# IO.net
KiCad netlist of a schematic drawn in Altium Designer
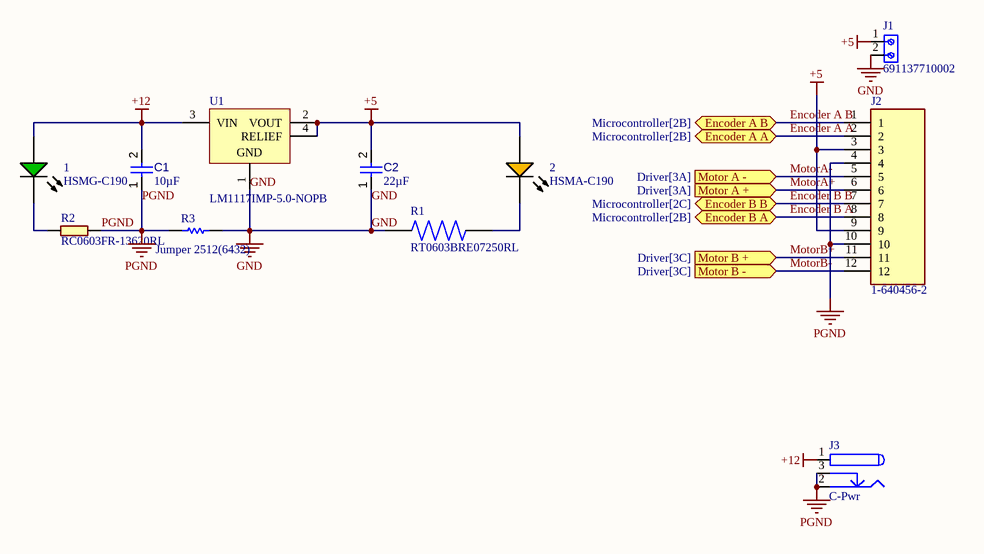
[diagram p0: IO.SchDoc]

(export (version "E")
  (design (tool "Eeschema 10.0.6"))
  (components
    (comp (ref "1")
      (value "HSMG-C190")
      (footprint "AVAG-HSMX-C190_V")
      (description "LED Uni-Color Green, 52 mW, 20 mA, -40 to 85 degC, 2-Pin SMD, RoHS, Tape and Reel")
      (fields (field (name "POWER") "52mW") (field (name "MANUFACTURER") "Avago"))
      (libsource (lib "Ryan Nedjabat") (part "LED-GREEN-AK-2"))
    )
    (comp (ref "2")
      (value "HSMA-C190")
      (footprint "AVAG-HSMX-C190_V")
      (description "LED Uni-Color Amber, 60 mW, 20 mA, -40 to 85 degC, 2-Pin SMD, RoHS, Tape and Reel")
      (fields (field (name "POWER") "60mW") (field (name "MANUFACTURER") "Avago"))
      (libsource (lib "Ryan Nedjabat") (part "LED-AMBER-AK-2"))
    )
    (comp (ref "C1")
      (value "10µF")
      (footprint "CAPC0603(1608)100_L")
      (description "Chip Capacitor, 10µF +/-20%, 10V, 0603, Thickness 1 mm")
      (fields (field (name "TOLERANCE") "10%") (field (name "Comment") "Capacitor 10µF +/-20% 10V 0603"))
      (libsource (lib "Ryan Nedjabat") (part "CAP-NP-2"))
    )
    (comp (ref "C2")
      (value "22µF")
      (footprint "CAPC0805(2012)145_L")
      (description "Chip Capacitor, 22µF +/-40%, 16V, 0805, Thickness 1.45 mm")
      (fields (field (name "TOLERANCE") "5%") (field (name "Comment") "Capacitor 22µF +/-40% 16V 0805"))
      (libsource (lib "Ryan Nedjabat") (part "CAP-NP-2"))
    )
    (comp (ref "J1")
      (value "691137710002")
      (footprint "691137710002")
      (description "2 Position Wire to Board Terminal Block Horizontal with Board 0.197 (5.00mm) Through Hole")
      (fields (field (name "MF") "WÃ¼rth Elektronik"))
      (libsource (lib "NeededParts") (part "691137710002"))
    )
    (comp (ref "J2")
      (value "1-640456-2")
      (footprint "TE_1-640456-2")
      (libsource (lib "NeededParts") (part "1-640456-2"))
    )
    (comp (ref "J3")
      (value "C-Pwr")
      (footprint "KLD_XLGE1.2")
      (description "Low Voltage Power Supply Connector")
      (fields (field (name "PUBLISHER") "Altium Limited"))
      (libsource (lib "PartsDatabaseV16.1") (part "C-Pwr"))
    )
    (comp (ref "R1")
      (value "RT0603BRE07250RL")
      (footprint "RESC1608X55N")
      (description "250 Ohms Â±0.1% 0.1W, 1/10W Chip Resistor 0603 (1608 Metric) - Thin Film")
      (fields (field (name "MF") "Yageo"))
      (libsource (lib "NeededParts") (part "RT0603BRE07250RL"))
    )
    (comp (ref "R2")
      (value "RC0603FR-13620RL")
      (footprint "0603")
      (description "https://octopart.com/rc0603fr-13100kl-yageo-12819546")
      (libsource (lib "NeededParts") (part "RC0603FR-13620RL"))
    )
    (comp (ref "R3")
      (value "Jumper 2512(6432)")
      (footprint "RESC2512(6432)_L")
      (description "Jumper 2512 (6432 Metric)")
      (fields (field (name "TOLERANCE") "None"))
      (libsource (lib "Altium Content Vault") (part "RES"))
    )
    (comp (ref "U1")
      (value "LM1117IMP-5.0-NOPB")
      (footprint "DCY0004A_M")
      (fields (field (name "MANUFACTURER") "Texas Instruments"))
      (libsource (lib "Ryan Nedjabat") (part "TI-LM1117-N-DCY-4"))
    )
  )
  (nets
    (net (code "1") (name "+5") (class "Default")
      (node (ref "2") (pin "1") (pinfunction "A_1") (pintype "passive"))
      (node (ref "C2") (pin "2") (pinfunction "2_2") (pintype "passive"))
      (node (ref "J1") (pin "1") (pinfunction "1_1") (pintype "passive"))
      (node (ref "J2") (pin "3") (pinfunction "3_3") (pintype "passive"))
      (node (ref "J2") (pin "9") (pinfunction "9_9") (pintype "passive"))
      (node (ref "U1") (pin "2") (pinfunction "VOUT_2") (pintype "power_in"))
      (node (ref "U1") (pin "4") (pinfunction "RELIEF_4") (pintype "power_in"))
    )
    (net (code "2") (name "+12") (class "Default")
      (node (ref "1") (pin "1") (pinfunction "A_1") (pintype "passive"))
      (node (ref "C1") (pin "2") (pinfunction "2_2") (pintype "passive"))
      (node (ref "J3") (pin "1") (pinfunction "1_1") (pintype "power_in"))
      (node (ref "U1") (pin "3") (pinfunction "VIN_3") (pintype "power_in"))
    )
    (net (code "3") (name "/Encoder A A") (class "Default")
      (node (ref "J2") (pin "2") (pinfunction "2_2") (pintype "passive"))
    )
    (net (code "4") (name "/Encoder A B") (class "Default")
      (node (ref "J2") (pin "1") (pinfunction "1_1") (pintype "passive"))
    )
    (net (code "5") (name "/Encoder B A") (class "Default")
      (node (ref "J2") (pin "8") (pinfunction "8_8") (pintype "passive"))
    )
    (net (code "6") (name "/Encoder B B") (class "Default")
      (node (ref "J2") (pin "7") (pinfunction "7_7") (pintype "passive"))
    )
    (net (code "7") (name "/MotorA+") (class "Default")
      (node (ref "J2") (pin "6") (pinfunction "6_6") (pintype "passive"))
    )
    (net (code "8") (name "/MotorA-") (class "Default")
      (node (ref "J2") (pin "5") (pinfunction "5_5") (pintype "passive"))
    )
    (net (code "9") (name "/MotorB+") (class "Default")
      (node (ref "J2") (pin "11") (pinfunction "11_11") (pintype "passive"))
    )
    (net (code "10") (name "/MotorB-") (class "Default")
      (node (ref "J2") (pin "12") (pinfunction "12_12") (pintype "passive"))
    )
    (net (code "11") (name "GND") (class "Default")
      (node (ref "C2") (pin "1") (pinfunction "1_1") (pintype "passive"))
      (node (ref "J1") (pin "2") (pinfunction "2_2") (pintype "passive"))
      (node (ref "R1") (pin "1") (pinfunction "1_1") (pintype "passive"))
      (node (ref "R3") (pin "2") (pinfunction "2_2") (pintype "passive"))
      (node (ref "U1") (pin "1") (pinfunction "GND_1") (pintype "power_in"))
    )
    (net (code "12") (name "Net-(1-K)") (class "Default")
      (node (ref "1") (pin "2") (pinfunction "K_2") (pintype "passive"))
      (node (ref "R2") (pin "1") (pinfunction "1_1") (pintype "passive"))
    )
    (net (code "13") (name "Net-(2-K)") (class "Default")
      (node (ref "2") (pin "2") (pinfunction "K_2") (pintype "passive"))
      (node (ref "R1") (pin "2") (pinfunction "2_2") (pintype "passive"))
    )
    (net (code "14") (name "PGND") (class "Default")
      (node (ref "C1") (pin "1") (pinfunction "1_1") (pintype "passive"))
      (node (ref "J2") (pin "10") (pinfunction "10_10") (pintype "passive"))
      (node (ref "J2") (pin "4") (pinfunction "4_4") (pintype "passive"))
      (node (ref "J3") (pin "2") (pinfunction "2_2") (pintype "power_in"))
      (node (ref "J3") (pin "3") (pinfunction "3_3") (pintype "power_in"))
      (node (ref "R2") (pin "2") (pinfunction "2_2") (pintype "passive"))
      (node (ref "R3") (pin "1") (pinfunction "1_1") (pintype "passive"))
    )
  )
)
